# MCU.net
KiCad netlist of a schematic drawn in Altium Designer
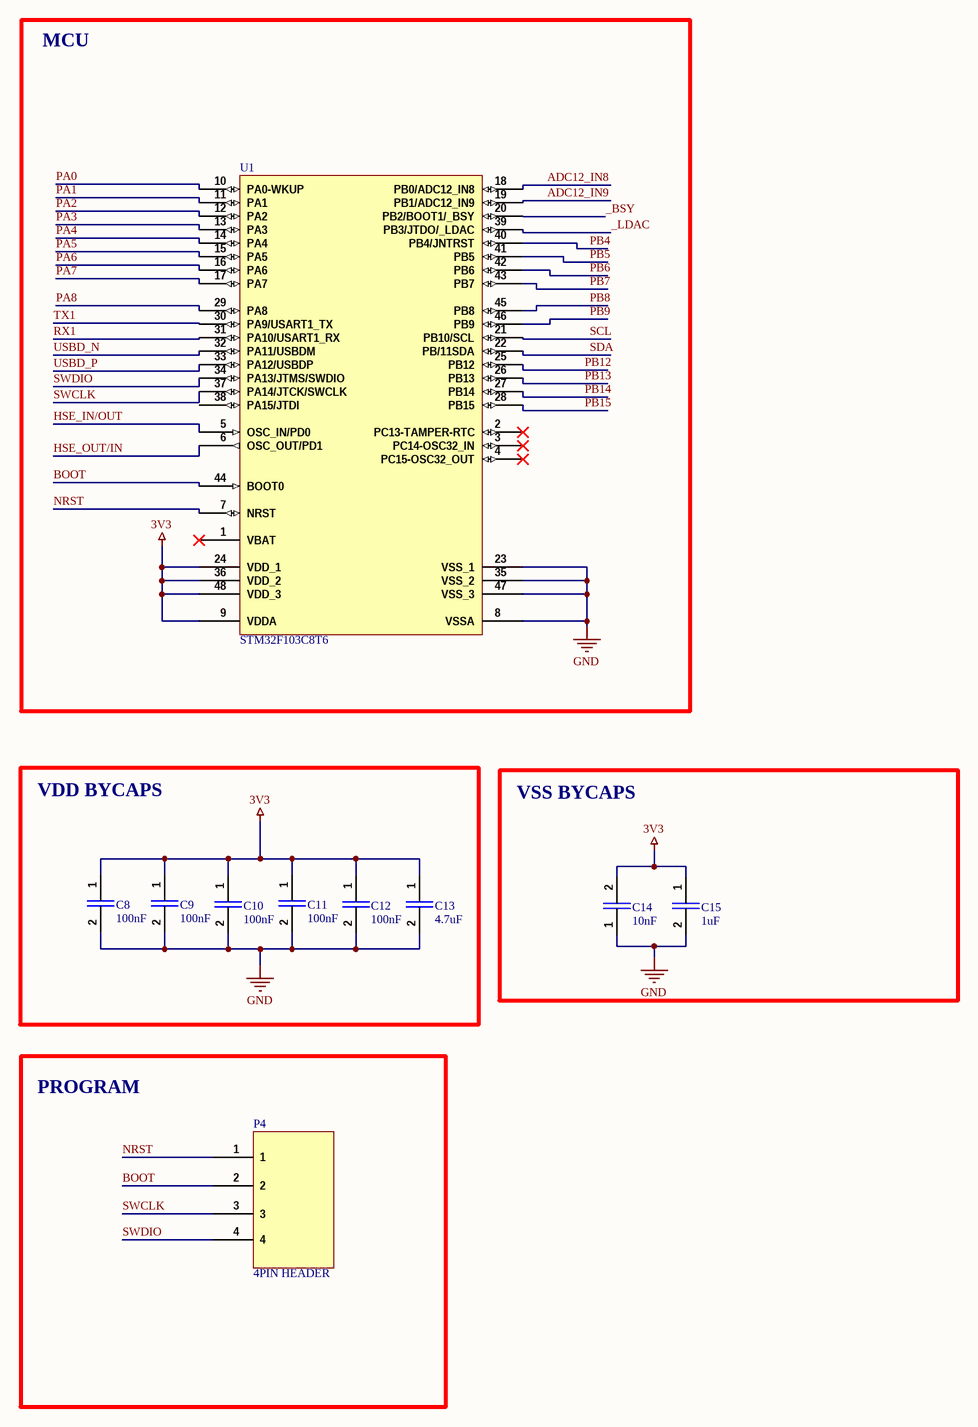
[diagram p0: MCU.SchDoc]

(export (version "E")
  (design (tool "Eeschema 10.0.6"))
  (components
    (comp (ref "C8")
      (value "100nF")
      (footprint "0603 Cap")
      (description "SMD 0603 (ceramic) capacitor")
      (fields
        (field (name "MANUFACTURER") "Murata")
        (field (name "MANUFACTURER PART NUMBER") "GRM21BR71C225KA12L")
      )
      (libsource (lib "Lib") (part "0603 Cap"))
    )
    (comp (ref "C9")
      (value "100nF")
      (footprint "0603 Cap")
      (description "SMD 0603 (ceramic) capacitor")
      (fields
        (field (name "MANUFACTURER") "Murata")
        (field (name "MANUFACTURER PART NUMBER") "GRM21BR71C225KA12L")
      )
      (libsource (lib "Lib") (part "0603 Cap"))
    )
    (comp (ref "C10")
      (value "100nF")
      (footprint "0603 Cap")
      (description "SMD 0603 (ceramic) capacitor")
      (fields
        (field (name "MANUFACTURER") "Murata")
        (field (name "MANUFACTURER PART NUMBER") "GRM21BR71C225KA12L")
      )
      (libsource (lib "Lib") (part "0603 Cap"))
    )
    (comp (ref "C11")
      (value "100nF")
      (footprint "0603 Cap")
      (description "SMD 0603 (ceramic) capacitor")
      (fields
        (field (name "MANUFACTURER") "Murata")
        (field (name "MANUFACTURER PART NUMBER") "GRM21BR71C225KA12L")
      )
      (libsource (lib "Lib") (part "0603 Cap"))
    )
    (comp (ref "C12")
      (value "100nF")
      (footprint "0603 Cap")
      (description "SMD 0603 (ceramic) capacitor")
      (fields
        (field (name "MANUFACTURER") "Murata")
        (field (name "MANUFACTURER PART NUMBER") "GRM21BR71C225KA12L")
      )
      (libsource (lib "Lib") (part "0603 Cap"))
    )
    (comp (ref "C13")
      (value "4.7uF")
      (footprint "0603 Cap")
      (description "SMD 0603 (ceramic) capacitor")
      (fields
        (field (name "MANUFACTURER") "Murata")
        (field (name "MANUFACTURER PART NUMBER") "GRM21BR71C225KA12L")
      )
      (libsource (lib "Lib") (part "0603 Cap"))
    )
    (comp (ref "C14")
      (value "10nF")
      (footprint "0603 Cap")
      (description "SMD 0603 (ceramic) capacitor")
      (fields
        (field (name "MANUFACTURER") "Murata")
        (field (name "MANUFACTURER PART NUMBER") "GRM21BR71C225KA12L")
      )
      (libsource (lib "Lib") (part "0603 Cap"))
    )
    (comp (ref "C15")
      (value "1uF")
      (footprint "0603 Cap")
      (description "SMD 0603 (ceramic) capacitor")
      (fields
        (field (name "MANUFACTURER") "Murata")
        (field (name "MANUFACTURER PART NUMBER") "GRM21BR71C225KA12L")
      )
      (libsource (lib "Lib") (part "0603 Cap"))
    )
    (comp (ref "P4")
      (value "4PIN HEADER")
      (footprint "SM04B-SRSS-TB")
      (libsource (lib "Lib") (part "4X HEADER"))
    )
    (comp (ref "U1")
      (value "STM32F103C8T6")
      (footprint "LQFP48_N")
      (description "STM32 ARM-based 32-bit MCU with 64 Kbytes Flash, 48-pin LQFP, Industrial Temperature")
      (fields (field (name "PUBLISHER") "Altium Limited"))
      (libsource (lib "ST Microcontroller 32-Bit STM32") (part "STM32F103C8T6"))
    )
  )
  (nets
    (net (code "1") (name "/ADC12_IN8") (class "Default")
      (node (ref "U1") (pin "18") (pinfunction "PB0/ADC12_IN8_18") (pintype "bidirectional"))
    )
    (net (code "2") (name "/ADC12_IN9") (class "Default")
      (node (ref "U1") (pin "19") (pinfunction "PB1/ADC12_IN9_19") (pintype "bidirectional"))
    )
    (net (code "3") (name "/BOOT") (class "Default")
      (node (ref "P4") (pin "2") (pinfunction "2_2") (pintype "passive"))
      (node (ref "U1") (pin "44") (pinfunction "BOOT0_44") (pintype "input"))
    )
    (net (code "4") (name "/HSE_IN{slash}OUT") (class "Default")
      (node (ref "U1") (pin "5") (pinfunction "OSC_IN/PD0_5") (pintype "input"))
    )
    (net (code "5") (name "/HSE_OUT{slash}IN") (class "Default")
      (node (ref "U1") (pin "6") (pinfunction "OSC_OUT/PD1_6") (pintype "output"))
    )
    (net (code "6") (name "/NRST") (class "Default")
      (node (ref "P4") (pin "1") (pinfunction "1_1") (pintype "passive"))
      (node (ref "U1") (pin "7") (pinfunction "NRST_7") (pintype "bidirectional"))
    )
    (net (code "7") (name "/PA0") (class "Default")
      (node (ref "U1") (pin "10") (pinfunction "PA0-WKUP_10") (pintype "bidirectional"))
    )
    (net (code "8") (name "/PA1") (class "Default")
      (node (ref "U1") (pin "11") (pinfunction "PA1_11") (pintype "bidirectional"))
    )
    (net (code "9") (name "/PA2") (class "Default")
      (node (ref "U1") (pin "12") (pinfunction "PA2_12") (pintype "bidirectional"))
    )
    (net (code "10") (name "/PA3") (class "Default")
      (node (ref "U1") (pin "13") (pinfunction "PA3_13") (pintype "bidirectional"))
    )
    (net (code "11") (name "/PA4") (class "Default")
      (node (ref "U1") (pin "14") (pinfunction "PA4_14") (pintype "bidirectional"))
    )
    (net (code "12") (name "/PA5") (class "Default")
      (node (ref "U1") (pin "15") (pinfunction "PA5_15") (pintype "bidirectional"))
    )
    (net (code "13") (name "/PA6") (class "Default")
      (node (ref "U1") (pin "16") (pinfunction "PA6_16") (pintype "bidirectional"))
    )
    (net (code "14") (name "/PA7") (class "Default")
      (node (ref "U1") (pin "17") (pinfunction "PA7_17") (pintype "bidirectional"))
    )
    (net (code "15") (name "/PA8") (class "Default")
      (node (ref "U1") (pin "29") (pinfunction "PA8_29") (pintype "bidirectional"))
    )
    (net (code "16") (name "/PB4") (class "Default")
      (node (ref "U1") (pin "40") (pinfunction "PB4/JNTRST_40") (pintype "bidirectional"))
    )
    (net (code "17") (name "/PB5") (class "Default")
      (node (ref "U1") (pin "41") (pinfunction "PB5_41") (pintype "bidirectional"))
    )
    (net (code "18") (name "/PB6") (class "Default")
      (node (ref "U1") (pin "42") (pinfunction "PB6_42") (pintype "bidirectional"))
    )
    (net (code "19") (name "/PB7") (class "Default")
      (node (ref "U1") (pin "43") (pinfunction "PB7_43") (pintype "bidirectional"))
    )
    (net (code "20") (name "/PB8") (class "Default")
      (node (ref "U1") (pin "45") (pinfunction "PB8_45") (pintype "bidirectional"))
    )
    (net (code "21") (name "/PB9") (class "Default")
      (node (ref "U1") (pin "46") (pinfunction "PB9_46") (pintype "bidirectional"))
    )
    (net (code "22") (name "/PB12") (class "Default")
      (node (ref "U1") (pin "25") (pinfunction "PB12_25") (pintype "bidirectional"))
    )
    (net (code "23") (name "/PB13") (class "Default")
      (node (ref "U1") (pin "26") (pinfunction "PB13_26") (pintype "bidirectional"))
    )
    (net (code "24") (name "/PB14") (class "Default")
      (node (ref "U1") (pin "27") (pinfunction "PB14_27") (pintype "bidirectional"))
    )
    (net (code "25") (name "/PB15") (class "Default")
      (node (ref "U1") (pin "28") (pinfunction "PB15_28") (pintype "bidirectional"))
    )
    (net (code "26") (name "/RX1") (class "Default")
      (node (ref "U1") (pin "31") (pinfunction "PA10/USART1_RX_31") (pintype "bidirectional"))
    )
    (net (code "27") (name "/SCL") (class "Default")
      (node (ref "U1") (pin "21") (pinfunction "PB10/SCL_21") (pintype "bidirectional"))
    )
    (net (code "28") (name "/SDA") (class "Default")
      (node (ref "U1") (pin "22") (pinfunction "PB/11SDA_22") (pintype "bidirectional"))
    )
    (net (code "29") (name "/SWCLK") (class "Default")
      (node (ref "P4") (pin "3") (pinfunction "3_3") (pintype "passive"))
      (node (ref "U1") (pin "37") (pinfunction "PA14/JTCK/SWCLK_37") (pintype "bidirectional"))
    )
    (net (code "30") (name "/SWDIO") (class "Default")
      (node (ref "P4") (pin "4") (pinfunction "4_4") (pintype "passive"))
      (node (ref "U1") (pin "34") (pinfunction "PA13/JTMS/SWDIO_34") (pintype "bidirectional"))
    )
    (net (code "31") (name "/TX1") (class "Default")
      (node (ref "U1") (pin "30") (pinfunction "PA9/USART1_TX_30") (pintype "bidirectional"))
    )
    (net (code "32") (name "/USBD_N") (class "Default")
      (node (ref "U1") (pin "32") (pinfunction "PA11/USBDM_32") (pintype "bidirectional"))
    )
    (net (code "33") (name "/USBD_P") (class "Default")
      (node (ref "U1") (pin "33") (pinfunction "PA12/USBDP_33") (pintype "bidirectional"))
    )
    (net (code "34") (name "/_BSY") (class "Default")
      (node (ref "U1") (pin "20") (pinfunction "PB2/BOOT1/_BSY_20") (pintype "bidirectional"))
    )
    (net (code "35") (name "/_LDAC") (class "Default")
      (node (ref "U1") (pin "39") (pinfunction "PB3/JTDO/_LDAC_39") (pintype "bidirectional"))
    )
    (net (code "36") (name "3V3") (class "Default")
      (node (ref "C10") (pin "1") (pinfunction "11_1") (pintype "passive"))
      (node (ref "C11") (pin "1") (pinfunction "11_1") (pintype "passive"))
      (node (ref "C12") (pin "1") (pinfunction "11_1") (pintype "passive"))
      (node (ref "C13") (pin "1") (pinfunction "11_1") (pintype "passive"))
      (node (ref "C14") (pin "2") (pinfunction "12_2") (pintype "passive"))
      (node (ref "C15") (pin "1") (pinfunction "11_1") (pintype "passive"))
      (node (ref "C8") (pin "1") (pinfunction "11_1") (pintype "passive"))
      (node (ref "C9") (pin "1") (pinfunction "11_1") (pintype "passive"))
      (node (ref "U1") (pin "24") (pinfunction "VDD_1_24") (pintype "power_in"))
      (node (ref "U1") (pin "36") (pinfunction "VDD_2_36") (pintype "power_in"))
      (node (ref "U1") (pin "48") (pinfunction "VDD_3_48") (pintype "power_in"))
      (node (ref "U1") (pin "9") (pinfunction "VDDA_9") (pintype "power_in"))
    )
    (net (code "37") (name "GND") (class "Default")
      (node (ref "C10") (pin "2") (pinfunction "12_2") (pintype "passive"))
      (node (ref "C11") (pin "2") (pinfunction "12_2") (pintype "passive"))
      (node (ref "C12") (pin "2") (pinfunction "12_2") (pintype "passive"))
      (node (ref "C13") (pin "2") (pinfunction "12_2") (pintype "passive"))
      (node (ref "C14") (pin "1") (pinfunction "11_1") (pintype "passive"))
      (node (ref "C15") (pin "2") (pinfunction "12_2") (pintype "passive"))
      (node (ref "C8") (pin "2") (pinfunction "12_2") (pintype "passive"))
      (node (ref "C9") (pin "2") (pinfunction "12_2") (pintype "passive"))
      (node (ref "U1") (pin "23") (pinfunction "VSS_1_23") (pintype "power_in"))
      (node (ref "U1") (pin "35") (pinfunction "VSS_2_35") (pintype "power_in"))
      (node (ref "U1") (pin "47") (pinfunction "VSS_3_47") (pintype "power_in"))
      (node (ref "U1") (pin "8") (pinfunction "VSSA_8") (pintype "power_in"))
    )
    (net (code "38") (name "unconnected-(U1-PA15{slash}JTDI-Pad38)") (class "Default")
      (node (ref "U1") (pin "38") (pinfunction "PA15/JTDI_38") (pintype "bidirectional"))
    )
    (net (code "39") (name "unconnected-(U1-PC13-TAMPER-RTC-Pad2)") (class "Default")
      (node (ref "U1") (pin "2") (pinfunction "PC13-TAMPER-RTC_2") (pintype "bidirectional+no_connect"))
    )
    (net (code "40") (name "unconnected-(U1-PC14-OSC32_IN-Pad3)") (class "Default")
      (node (ref "U1") (pin "3") (pinfunction "PC14-OSC32_IN_3") (pintype "bidirectional+no_connect"))
    )
    (net (code "41") (name "unconnected-(U1-PC15-OSC32_OUT-Pad4)") (class "Default")
      (node (ref "U1") (pin "4") (pinfunction "PC15-OSC32_OUT_4") (pintype "bidirectional+no_connect"))
    )
    (net (code "42") (name "unconnected-(U1-VBAT-Pad1)") (class "Default")
      (node (ref "U1") (pin "1") (pinfunction "VBAT_1") (pintype "power_in+no_connect"))
    )
  )
)
